# INTERFACE.net
KiCad netlist of a schematic drawn in Altium Designer
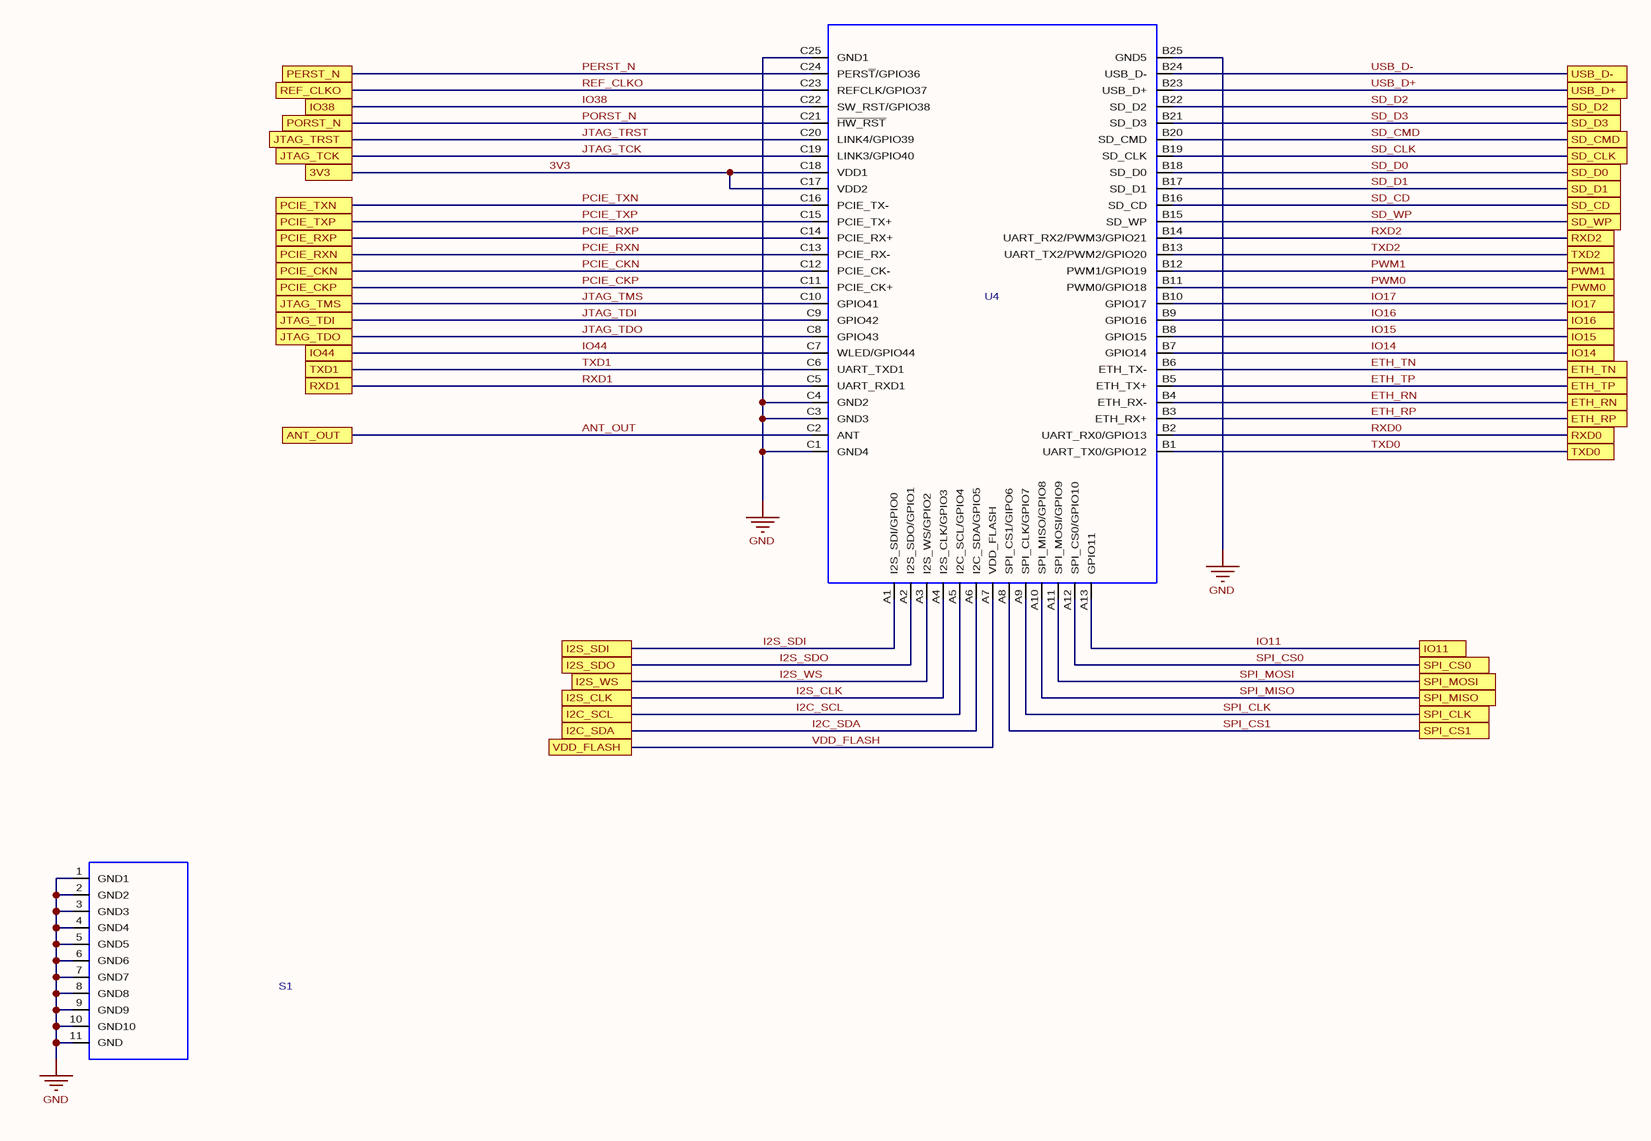
[diagram p0: INTERFACE.SchDoc]

(export (version "E")
  (design (tool "Eeschema 10.0.6"))
  (components
    (comp (ref "S1")
      (value "O2S-SHIELD")
      (footprint "O2S-SHIELD")
      (description "O2S SHIELD")
      (fields (field (name "MANUFACTURER") "RYSE Inc."))
      (libsource (lib "*") (part "O2S-SHIELD"))
    )
    (comp (ref "U4")
      (value "OMEGA2S-PCB")
      (footprint "OMEGA2S+PCB")
      (description "RX TXRX MODULE WIFI U.FL SMD")
      (fields (field (name "MANUFACTURER") "Onion Corporation") (field (name "PART NUMBER") "OM-O2S"))
      (libsource (lib "*") (part "OMEGA2S-PCB"))
    )
  )
  (nets
    (net (code "1") (name "/3V3") (class "Default")
      (node (ref "U4") (pin "C17") (pinfunction "VDD2_C17") (pintype "passive"))
      (node (ref "U4") (pin "C18") (pinfunction "VDD1_C18") (pintype "passive"))
    )
    (net (code "2") (name "/ANT_OUT") (class "Default")
      (node (ref "U4") (pin "C2") (pinfunction "ANT_C2") (pintype "passive"))
    )
    (net (code "3") (name "/ETH_RN") (class "Default")
      (node (ref "U4") (pin "B4") (pinfunction "ETH_RX-_B4") (pintype "passive"))
    )
    (net (code "4") (name "/ETH_RP") (class "Default")
      (node (ref "U4") (pin "B3") (pinfunction "ETH_RX+_B3") (pintype "passive"))
    )
    (net (code "5") (name "/ETH_TN") (class "Default")
      (node (ref "U4") (pin "B6") (pinfunction "ETH_TX-_B6") (pintype "passive"))
    )
    (net (code "6") (name "/ETH_TP") (class "Default")
      (node (ref "U4") (pin "B5") (pinfunction "ETH_TX+_B5") (pintype "passive"))
    )
    (net (code "7") (name "/I2C_SCL") (class "Default")
      (node (ref "U4") (pin "A5") (pinfunction "I2C_SCL/GPIO4_A5") (pintype "passive"))
    )
    (net (code "8") (name "/I2C_SDA") (class "Default")
      (node (ref "U4") (pin "A6") (pinfunction "I2C_SDA/GPIO5_A6") (pintype "passive"))
    )
    (net (code "9") (name "/I2S_CLK") (class "Default")
      (node (ref "U4") (pin "A4") (pinfunction "I2S_CLK/GPIO3_A4") (pintype "passive"))
    )
    (net (code "10") (name "/I2S_SDI") (class "Default")
      (node (ref "U4") (pin "A1") (pinfunction "I2S_SDI/GPIO0_A1") (pintype "passive"))
    )
    (net (code "11") (name "/I2S_SDO") (class "Default")
      (node (ref "U4") (pin "A2") (pinfunction "I2S_SDO/GPIO1_A2") (pintype "passive"))
    )
    (net (code "12") (name "/I2S_WS") (class "Default")
      (node (ref "U4") (pin "A3") (pinfunction "I2S_WS/GPIO2_A3") (pintype "passive"))
    )
    (net (code "13") (name "/IO11") (class "Default")
      (node (ref "U4") (pin "A13") (pinfunction "GPIO11_A13") (pintype "passive"))
    )
    (net (code "14") (name "/IO14") (class "Default")
      (node (ref "U4") (pin "B7") (pinfunction "GPIO14_B7") (pintype "passive"))
    )
    (net (code "15") (name "/IO15") (class "Default")
      (node (ref "U4") (pin "B8") (pinfunction "GPIO15_B8") (pintype "passive"))
    )
    (net (code "16") (name "/IO16") (class "Default")
      (node (ref "U4") (pin "B9") (pinfunction "GPIO16_B9") (pintype "passive"))
    )
    (net (code "17") (name "/IO17") (class "Default")
      (node (ref "U4") (pin "B10") (pinfunction "GPIO17_B10") (pintype "passive"))
    )
    (net (code "18") (name "/IO38") (class "Default")
      (node (ref "U4") (pin "C22") (pinfunction "SW_RST/GPIO38_C22") (pintype "passive"))
    )
    (net (code "19") (name "/IO44") (class "Default")
      (node (ref "U4") (pin "C7") (pinfunction "WLED/GPIO44_C7") (pintype "passive"))
    )
    (net (code "20") (name "/JTAG_TCK") (class "Default")
      (node (ref "U4") (pin "C19") (pinfunction "LINK3/GPIO40_C19") (pintype "passive"))
    )
    (net (code "21") (name "/JTAG_TDI") (class "Default")
      (node (ref "U4") (pin "C9") (pinfunction "GPIO42_C9") (pintype "passive"))
    )
    (net (code "22") (name "/JTAG_TDO") (class "Default")
      (node (ref "U4") (pin "C8") (pinfunction "GPIO43_C8") (pintype "passive"))
    )
    (net (code "23") (name "/JTAG_TMS") (class "Default")
      (node (ref "U4") (pin "C10") (pinfunction "GPIO41_C10") (pintype "passive"))
    )
    (net (code "24") (name "/JTAG_TRST") (class "Default")
      (node (ref "U4") (pin "C20") (pinfunction "LINK4/GPIO39_C20") (pintype "passive"))
    )
    (net (code "25") (name "/PCIE_CKN") (class "Default")
      (node (ref "U4") (pin "C12") (pinfunction "PCIE_CK-_C12") (pintype "passive"))
    )
    (net (code "26") (name "/PCIE_CKP") (class "Default")
      (node (ref "U4") (pin "C11") (pinfunction "PCIE_CK+_C11") (pintype "passive"))
    )
    (net (code "27") (name "/PCIE_RXN") (class "Default")
      (node (ref "U4") (pin "C13") (pinfunction "PCIE_RX-_C13") (pintype "passive"))
    )
    (net (code "28") (name "/PCIE_RXP") (class "Default")
      (node (ref "U4") (pin "C14") (pinfunction "PCIE_RX+_C14") (pintype "passive"))
    )
    (net (code "29") (name "/PCIE_TXN") (class "Default")
      (node (ref "U4") (pin "C16") (pinfunction "PCIE_TX-_C16") (pintype "passive"))
    )
    (net (code "30") (name "/PCIE_TXP") (class "Default")
      (node (ref "U4") (pin "C15") (pinfunction "PCIE_TX+_C15") (pintype "passive"))
    )
    (net (code "31") (name "/PERST_N") (class "Default")
      (node (ref "U4") (pin "C24") (pinfunction "PERS~{T}/GPIO36_C24") (pintype "passive"))
    )
    (net (code "32") (name "/PORST_N") (class "Default")
      (node (ref "U4") (pin "C21") (pinfunction "HW_RST_C21") (pintype "passive"))
    )
    (net (code "33") (name "/PWM0") (class "Default")
      (node (ref "U4") (pin "B11") (pinfunction "PWM0/GPIO18_B11") (pintype "passive"))
    )
    (net (code "34") (name "/PWM1") (class "Default")
      (node (ref "U4") (pin "B12") (pinfunction "PWM1/GPIO19_B12") (pintype "passive"))
    )
    (net (code "35") (name "/REF_CLKO") (class "Default")
      (node (ref "U4") (pin "C23") (pinfunction "REFCLK/GPIO37_C23") (pintype "passive"))
    )
    (net (code "36") (name "/RXD0") (class "Default")
      (node (ref "U4") (pin "B2") (pinfunction "UART_RX0/GPIO13_B2") (pintype "passive"))
    )
    (net (code "37") (name "/RXD1") (class "Default")
      (node (ref "U4") (pin "C5") (pinfunction "UART_RXD1_C5") (pintype "passive"))
    )
    (net (code "38") (name "/RXD2") (class "Default")
      (node (ref "U4") (pin "B14") (pinfunction "UART_RX2/PWM3/GPIO21_B14") (pintype "passive"))
    )
    (net (code "39") (name "/SD_CD") (class "Default")
      (node (ref "U4") (pin "B16") (pinfunction "SD_CD_B16") (pintype "passive"))
    )
    (net (code "40") (name "/SD_CLK") (class "Default")
      (node (ref "U4") (pin "B19") (pinfunction "SD_CLK_B19") (pintype "passive"))
    )
    (net (code "41") (name "/SD_CMD") (class "Default")
      (node (ref "U4") (pin "B20") (pinfunction "SD_CMD_B20") (pintype "passive"))
    )
    (net (code "42") (name "/SD_D0") (class "Default")
      (node (ref "U4") (pin "B18") (pinfunction "SD_D0_B18") (pintype "passive"))
    )
    (net (code "43") (name "/SD_D1") (class "Default")
      (node (ref "U4") (pin "B17") (pinfunction "SD_D1_B17") (pintype "passive"))
    )
    (net (code "44") (name "/SD_D2") (class "Default")
      (node (ref "U4") (pin "B22") (pinfunction "SD_D2_B22") (pintype "passive"))
    )
    (net (code "45") (name "/SD_D3") (class "Default")
      (node (ref "U4") (pin "B21") (pinfunction "SD_D3_B21") (pintype "passive"))
    )
    (net (code "46") (name "/SD_WP") (class "Default")
      (node (ref "U4") (pin "B15") (pinfunction "SD_WP_B15") (pintype "passive"))
    )
    (net (code "47") (name "/SPI_CLK") (class "Default")
      (node (ref "U4") (pin "A9") (pinfunction "SPI_CLK/GPIO7_A9") (pintype "passive"))
    )
    (net (code "48") (name "/SPI_CS0") (class "Default")
      (node (ref "U4") (pin "A12") (pinfunction "SPI_CS0/GPIO10_A12") (pintype "passive"))
    )
    (net (code "49") (name "/SPI_CS1") (class "Default")
      (node (ref "U4") (pin "A8") (pinfunction "SPI_CS1/GIPO6_A8") (pintype "passive"))
    )
    (net (code "50") (name "/SPI_MISO") (class "Default")
      (node (ref "U4") (pin "A10") (pinfunction "SPI_MISO/GPIO8_A10") (pintype "passive"))
    )
    (net (code "51") (name "/SPI_MOSI") (class "Default")
      (node (ref "U4") (pin "A11") (pinfunction "SPI_MOSI/GPIO9_A11") (pintype "passive"))
    )
    (net (code "52") (name "/TXD0") (class "Default")
      (node (ref "U4") (pin "B1") (pinfunction "UART_TX0/GPIO12_B1") (pintype "passive"))
    )
    (net (code "53") (name "/TXD1") (class "Default")
      (node (ref "U4") (pin "C6") (pinfunction "UART_TXD1_C6") (pintype "passive"))
    )
    (net (code "54") (name "/TXD2") (class "Default")
      (node (ref "U4") (pin "B13") (pinfunction "UART_TX2/PWM2/GPIO20_B13") (pintype "passive"))
    )
    (net (code "55") (name "/USB_D+") (class "Default")
      (node (ref "U4") (pin "B23") (pinfunction "USB_D+_B23") (pintype "passive"))
    )
    (net (code "56") (name "/USB_D-") (class "Default")
      (node (ref "U4") (pin "B24") (pinfunction "USB_D-_B24") (pintype "passive"))
    )
    (net (code "57") (name "/VDD_FLASH") (class "Default")
      (node (ref "U4") (pin "A7") (pinfunction "VDD_FLASH_A7") (pintype "passive"))
    )
    (net (code "58") (name "GND") (class "Default")
      (node (ref "S1") (pin "1") (pinfunction "GND1_1") (pintype "passive"))
      (node (ref "S1") (pin "10") (pinfunction "GND10_10") (pintype "passive"))
      (node (ref "S1") (pin "11") (pinfunction "GND_11") (pintype "passive"))
      (node (ref "S1") (pin "2") (pinfunction "GND2_2") (pintype "passive"))
      (node (ref "S1") (pin "3") (pinfunction "GND3_3") (pintype "passive"))
      (node (ref "S1") (pin "4") (pinfunction "GND4_4") (pintype "passive"))
      (node (ref "S1") (pin "5") (pinfunction "GND5_5") (pintype "passive"))
      (node (ref "S1") (pin "6") (pinfunction "GND6_6") (pintype "passive"))
      (node (ref "S1") (pin "7") (pinfunction "GND7_7") (pintype "passive"))
      (node (ref "S1") (pin "8") (pinfunction "GND8_8") (pintype "passive"))
      (node (ref "S1") (pin "9") (pinfunction "GND9_9") (pintype "passive"))
      (node (ref "U4") (pin "B25") (pinfunction "GND5_B25") (pintype "passive"))
      (node (ref "U4") (pin "C1") (pinfunction "GND4_C1") (pintype "passive"))
      (node (ref "U4") (pin "C25") (pinfunction "GND1_C25") (pintype "passive"))
      (node (ref "U4") (pin "C3") (pinfunction "GND3_C3") (pintype "passive"))
      (node (ref "U4") (pin "C4") (pinfunction "GND2_C4") (pintype "passive"))
    )
  )
)
